# v1_1.net
KiCad netlist of a schematic drawn in Altium Designer
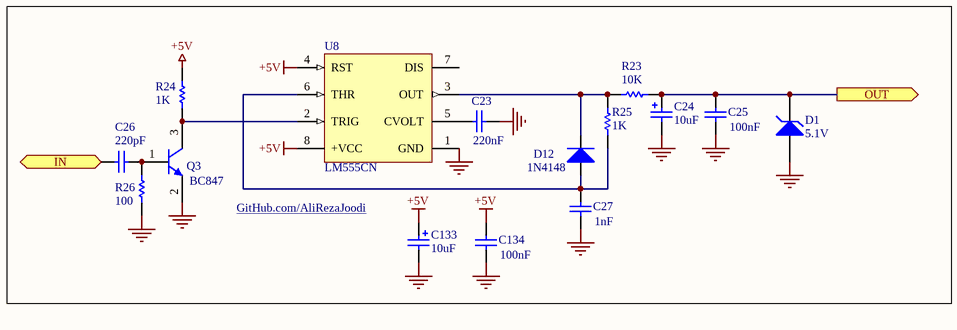
[diagram p0: v1.1.SchDoc]

(export (version "E")
  (design (tool "Eeschema 10.0.6"))
  (components
    (comp (ref "C23")
      (value "220nF")
      (footprint "RESC3216N")
      (description "Capacitor")
      (fields (field (name "Comment") "Cap") (field (name "PUBLISHER") "Altium Limited"))
      (libsource (lib "") (part "Cap_1"))
    )
    (comp (ref "C24")
      (value "10uF")
      (footprint "Cap_B")
      (description "Polarized Capacitor (Radial)")
      (fields
        (field (name "MANUFACTURER") "Generic Components")
        (field (name "Comment") "Cap Pol1")
        (field (name "PUBLISHER") "Altium Limited")
      )
      (libsource (lib "Miscellaneous Devices") (part "Cap Pol1"))
    )
    (comp (ref "C25")
      (value "100nF")
      (footprint "0805")
      (description "Capacitor")
      (fields (field (name "Comment") "Cap") (field (name "PUBLISHER") "Altium Limited"))
      (libsource (lib "Miscellaneous Devices") (part "Cap"))
    )
    (comp (ref "C26")
      (value "220pF")
      (footprint "RESC3216N")
      (description "Capacitor")
      (fields (field (name "Comment") "Cap") (field (name "PUBLISHER") "Altium Limited"))
      (libsource (lib "") (part "Cap_1"))
    )
    (comp (ref "C27")
      (value "1nF")
      (footprint "RESC3216N")
      (description "Capacitor")
      (fields (field (name "Comment") "Cap") (field (name "PUBLISHER") "Altium Limited"))
      (libsource (lib "Miscellaneous Devices") (part "Cap"))
    )
    (comp (ref "C133")
      (value "10uF")
      (footprint "Cap_B")
      (description "Polarized Capacitor (Radial)")
      (fields
        (field (name "MANUFACTURER") "Generic Components")
        (field (name "Comment") "Capacitor")
        (field (name "PUBLISHER") "Altium Limited")
      )
      (libsource (lib "Miscellaneous Devices") (part "Cap Pol1"))
    )
    (comp (ref "C134")
      (value "100nF")
      (footprint "0805")
      (description "Capacitor")
      (fields (field (name "Comment") "Cap") (field (name "PUBLISHER") "Altium Limited"))
      (libsource (lib "Miscellaneous Devices") (part "Cap"))
    )
    (comp (ref "D1")
      (value "5.1V")
      (footprint "MELF-D3516-1406")
      (description "Zener Diode")
      (fields
        (field (name "MANUFACTURER") "Generic Components")
        (field (name "Comment") "Diode")
        (field (name "PUBLISHER") "Altium Limited")
      )
      (libsource (lib "Miscellaneous Devices") (part "D Zener"))
    )
    (comp (ref "D12")
      (value "1N4148")
      (footprint "0805_Diode")
      (description "Default Diode")
      (fields
        (field (name "MANUFACTURER") "Generic Components")
        (field (name "Comment") "Diode")
        (field (name "PUBLISHER") "Altium Limited")
      )
      (libsource (lib "Miscellaneous Devices") (part "Diode"))
    )
    (comp (ref "Q3")
      (value "BC847")
      (footprint "SOT23-3N")
      (description "Silicon Bipolar Transistor")
      (fields (field (name "Comment") "NPN"))
      (libsource (lib "my Libraries") (part "BC847"))
    )
    (comp (ref "R23")
      (value "10K")
      (footprint "0805")
      (description "Resistor")
      (fields (field (name "Comment") "Res1") (field (name "PUBLISHER") "Altium Limited"))
      (libsource (lib "Miscellaneous Devices") (part "Res1"))
    )
    (comp (ref "R24")
      (value "1K")
      (footprint "0805")
      (description "Resistor")
      (fields (field (name "Comment") "Res1") (field (name "PUBLISHER") "Altium Limited"))
      (libsource (lib "Miscellaneous Devices") (part "Res1"))
    )
    (comp (ref "R25")
      (value "1K")
      (footprint "0805")
      (description "Resistor")
      (fields (field (name "Comment") "Res1") (field (name "PUBLISHER") "Altium Limited"))
      (libsource (lib "Miscellaneous Devices") (part "Res1"))
    )
    (comp (ref "R26")
      (value "100")
      (footprint "0805")
      (description "Resistor")
      (fields (field (name "Comment") "Res1") (field (name "PUBLISHER") "Altium Limited"))
      (libsource (lib "Miscellaneous Devices") (part "Res1"))
    )
    (comp (ref "U8")
      (value "LM555CN")
      (footprint "SOP127P636-8N")
      (description "Timer")
      (fields
        (field (name "MANUFACTURER") "National Semiconductor")
        (field (name "DIGIKEYPARTNUMBER") "LM555CNNS-ND")
        (field (name "PUBLISHER") "Altium Limited")
      )
      (libsource (lib "NSC Analog") (part "LM555CN"))
    )
  )
  (nets
    (net (code "1") (name "+5V") (class "Default")
      (node (ref "C133") (pin "1") (pinfunction "1_1") (pintype "passive"))
      (node (ref "C134") (pin "1") (pinfunction "1_1") (pintype "passive"))
      (node (ref "R24") (pin "1") (pinfunction "1_1") (pintype "passive"))
      (node (ref "U8") (pin "4") (pinfunction "RST_4") (pintype "input"))
      (node (ref "U8") (pin "8") (pinfunction "+VCC_8") (pintype "power_in"))
    )
    (net (code "2") (name "/IN") (class "Default")
      (node (ref "C26") (pin "2") (pinfunction "2_2") (pintype "passive"))
    )
    (net (code "3") (name "/OUT") (class "Default")
      (node (ref "C24") (pin "1") (pinfunction "1_1") (pintype "passive"))
      (node (ref "C25") (pin "1") (pinfunction "1_1") (pintype "passive"))
      (node (ref "D1") (pin "2") (pinfunction "K_2") (pintype "passive"))
      (node (ref "R23") (pin "2") (pinfunction "2_2") (pintype "passive"))
    )
    (net (code "4") (name "GND") (class "Default")
      (node (ref "C133") (pin "2") (pinfunction "2_2") (pintype "passive"))
      (node (ref "C134") (pin "2") (pinfunction "2_2") (pintype "passive"))
      (node (ref "C23") (pin "1") (pinfunction "1_1") (pintype "passive"))
      (node (ref "C24") (pin "2") (pinfunction "2_2") (pintype "passive"))
      (node (ref "C25") (pin "2") (pinfunction "2_2") (pintype "passive"))
      (node (ref "C27") (pin "2") (pinfunction "2_2") (pintype "passive"))
      (node (ref "D1") (pin "1") (pinfunction "A_1") (pintype "passive"))
      (node (ref "Q3") (pin "2") (pinfunction "E_2") (pintype "passive"))
      (node (ref "R26") (pin "2") (pinfunction "2_2") (pintype "passive"))
      (node (ref "U8") (pin "1") (pinfunction "GND_1") (pintype "power_in"))
    )
    (net (code "5") (name "Net-(D12-A)") (class "Default")
      (node (ref "C27") (pin "1") (pinfunction "1_1") (pintype "passive"))
      (node (ref "D12") (pin "1") (pinfunction "A_1") (pintype "passive"))
      (node (ref "R25") (pin "1") (pinfunction "1_1") (pintype "passive"))
      (node (ref "U8") (pin "6") (pinfunction "THR_6") (pintype "input"))
    )
    (net (code "6") (name "Net-(D12-K)") (class "Default")
      (node (ref "D12") (pin "2") (pinfunction "K_2") (pintype "passive"))
      (node (ref "R23") (pin "1") (pinfunction "1_1") (pintype "passive"))
      (node (ref "R25") (pin "2") (pinfunction "2_2") (pintype "passive"))
      (node (ref "U8") (pin "3") (pinfunction "OUT_3") (pintype "output"))
    )
    (net (code "7") (name "Net-(Q3-B)") (class "Default")
      (node (ref "C26") (pin "1") (pinfunction "1_1") (pintype "passive"))
      (node (ref "Q3") (pin "1") (pinfunction "B_1") (pintype "passive"))
      (node (ref "R26") (pin "1") (pinfunction "1_1") (pintype "passive"))
    )
    (net (code "8") (name "Net-(Q3-C)") (class "Default")
      (node (ref "Q3") (pin "3") (pinfunction "C_3") (pintype "passive"))
      (node (ref "R24") (pin "2") (pinfunction "2_2") (pintype "passive"))
      (node (ref "U8") (pin "2") (pinfunction "TRIG_2") (pintype "input"))
    )
    (net (code "9") (name "Net-(U8-CVOLT)") (class "Default")
      (node (ref "C23") (pin "2") (pinfunction "2_2") (pintype "passive"))
      (node (ref "U8") (pin "5") (pinfunction "CVOLT_5") (pintype "passive"))
    )
    (net (code "10") (name "unconnected-(U8-DIS-Pad7)") (class "Default")
      (node (ref "U8") (pin "7") (pinfunction "DIS_7") (pintype "open_collector"))
    )
  )
)
